# PowerSupply.net
KiCad netlist of a schematic drawn in Altium Designer
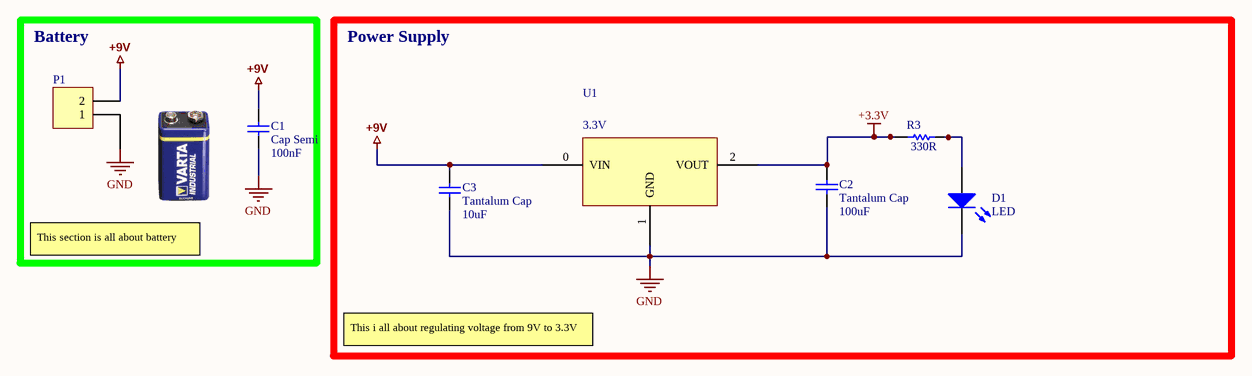
[diagram p0: PowerSupply.SchDoc]

(export (version "E")
  (design (tool "Eeschema 10.0.6"))
  (components
    (comp (ref "C1")
      (value "Cap Semi")
      (footprint "C1206")
      (description "Capacitor (Semiconductor SIM Model)")
      (fields (field (name "ALTIUM_VALUE") "100nF") (field (name "PUBLISHER") "Altium Limited"))
      (libsource (lib "Miscellaneous Devices") (part "Cap Semi"))
    )
    (comp (ref "C2")
      (value "Tantalum Cap")
      (footprint "C1206")
      (description "Capacitor (Semiconductor SIM Model)")
      (fields (field (name "ALTIUM_VALUE") "100uF") (field (name "PUBLISHER") "Altium Limited"))
      (libsource (lib "Miscellaneous Devices") (part "Cap Semi"))
    )
    (comp (ref "C3")
      (value "Tantalum Cap")
      (footprint "C1206")
      (description "Capacitor (Semiconductor SIM Model)")
      (fields (field (name "ALTIUM_VALUE") "10uF") (field (name "PUBLISHER") "Altium Limited"))
      (libsource (lib "Miscellaneous Devices") (part "Cap Semi"))
    )
    (comp (ref "D1")
      (value "LED")
      (footprint "MY_LED_0805")
      (description "Typical INFRARED GaAs LED")
      (fields (field (name "ASID PART NUMBER") "LED-AS"))
      (libsource (lib "Mylib+Rev+4") (part "LED"))
    )
    (comp (ref "P1")
      (value "~")
      (footprint "HDR1X2H")
      (description "Header, 2-Pin, Right Angle")
      (fields (field (name "VOLTAGE") "9V") (field (name "PUBLISHER") "Altium Limited"))
      (libsource (lib "smartmcu(1)") (part "Header 2H"))
    )
    (comp (ref "R3")
      (value "330R")
      (footprint "MY_0805")
      (description "Standard resistor")
      (fields (field (name "ASID PART NUMBER") "Res-AS"))
      (libsource (lib "Mylib+Rev+4") (part "Res"))
    )
    (comp (ref "U1")
      (value "~")
      (footprint "4-pin SOT")
      (fields (field (name "OUTPUT VOLTAGE") "3.3V"))
      (libsource (lib "PCB_Project") (part "LM1117"))
    )
  )
  (nets
    (net (code "1") (name "+3.3V") (class "Default")
      (node (ref "C2") (pin "2") (pinfunction "2_2") (pintype "passive"))
      (node (ref "R3") (pin "1") (pinfunction "1_1") (pintype "passive"))
      (node (ref "U1") (pin "2") (pinfunction "VOUT_2") (pintype "passive"))
    )
    (net (code "2") (name "+9V") (class "Default")
      (node (ref "C1") (pin "2") (pinfunction "2_2") (pintype "passive"))
      (node (ref "C3") (pin "2") (pinfunction "2_2") (pintype "passive"))
      (node (ref "P1") (pin "2") (pinfunction "2_2") (pintype "passive"))
      (node (ref "U1") (pin "0") (pinfunction "VIN_0") (pintype "passive"))
    )
    (net (code "3") (name "GND") (class "Default")
      (node (ref "C1") (pin "1") (pinfunction "1_1") (pintype "passive"))
      (node (ref "C2") (pin "1") (pinfunction "1_1") (pintype "passive"))
      (node (ref "C3") (pin "1") (pinfunction "1_1") (pintype "passive"))
      (node (ref "D1") (pin "K") (pinfunction "K_K") (pintype "passive"))
      (node (ref "P1") (pin "1") (pinfunction "1_1") (pintype "passive"))
      (node (ref "U1") (pin "1") (pinfunction "GND_1") (pintype "passive"))
    )
    (net (code "4") (name "Net-(D1-PadA)") (class "Default")
      (node (ref "D1") (pin "A") (pinfunction "A_A") (pintype "passive"))
      (node (ref "R3") (pin "2") (pinfunction "2_2") (pintype "passive"))
    )
  )
)
